# 5V_Regulator.net
KiCad netlist of a schematic drawn in Altium Designer
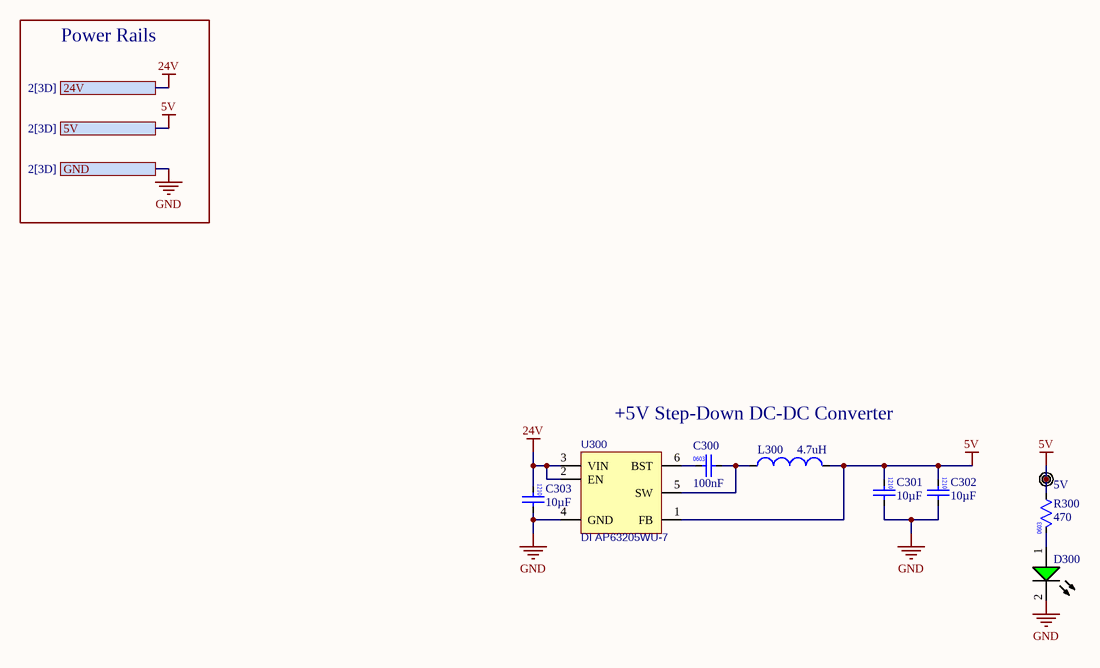
[diagram p0: 5V_Regulator.SchDoc]

(export (version "E")
  (design (tool "Eeschema 10.0.6"))
  (components
    (comp (ref "C300")
      (value "100nF")
      (footprint "0603 Capacitor Footprint")
      (description "CAP CER 0.1UF 50V X7R 0603")
      (fields (field (name "MANUFACTURER PART NUMBER") "CC0603JPX7R9BB104") (field (name "TOLERANCE") "5%"))
      (libsource (lib "UBC Formula Electric") (part "0603 Generic Ceramic Capacitor"))
    )
    (comp (ref "C301")
      (value "10µF")
      (footprint "1210 CAPACTIOR (TDK C-SERIES)")
      (description "Ceramic Capacitor, Multilayer, Ceramic, 50V, 10% Tol, X7R, 15% TC, 10uF, Surface Mount, 1210")
      (fields
        (field (name "TOLERANCE") "10%")
        (field (name "Comment") "1210 10uF 10% 50V")
        (field (name "SOURCE") "UBC Formula Electric.SchLib")
      )
      (libsource (lib "UBC Formula Electric") (part "1210 Generic Ceramic Capacitor"))
    )
    (comp (ref "C302")
      (value "10µF")
      (footprint "1210 CAPACTIOR (TDK C-SERIES)")
      (description "Ceramic Capacitor, Multilayer, Ceramic, 50V, 10% Tol, X7R, 15% TC, 10uF, Surface Mount, 1210")
      (fields
        (field (name "TOLERANCE") "10%")
        (field (name "Comment") "1210 10uF 10% 50V")
        (field (name "SOURCE") "UBC Formula Electric.SchLib")
      )
      (libsource (lib "UBC Formula Electric") (part "1210 Generic Ceramic Capacitor"))
    )
    (comp (ref "C303")
      (value "10µF")
      (footprint "1210 CAPACTIOR (TDK C-SERIES)")
      (description "Ceramic Capacitor, Multilayer, Ceramic, 50V, 10% Tol, X7R, 15% TC, 10uF, Surface Mount, 1210")
      (fields
        (field (name "TOLERANCE") "10%")
        (field (name "Comment") "1210 10uF 10% 50V")
        (field (name "SOURCE") "UBC Formula Electric.SchLib")
      )
      (libsource (lib "UBC Formula Electric") (part "1210 Generic Ceramic Capacitor"))
    )
    (comp (ref "D300")
      (value "Lite-On LTST-C193KGKT-5A")
      (footprint "Lite-On LTST-C193KGKT-5A GREEN (1608)")
      (description "LED GREEN CLEAR CHIP SMD")
      (fields (field (name "SOURCE") "UBC Formula Electric.SchLib"))
      (libsource (lib "UBC Formula Electric") (part "Lite-On LTST-C193KGKT-5A"))
    )
    (comp (ref "L300")
      (value "Bourns SRN6045-4R7Y")
      (footprint "BOURNS SRN6045-4R7Y")
      (description "FIXED IND 4.7UH 3A 37.6 MOHM SMD")
      (fields (field (name "INDUCTANCE") "4.7uH") (field (name "SOURCE") "UBC Formula Electric.SchLib"))
      (libsource (lib "UBC Formula Electric") (part "Symbol"))
    )
    (comp (ref "R300")
      (value "470")
      (footprint "0603 Resistor Footprint")
      (description "Res Thick Film 0603 470 Ohm 5% 0.25W(1/4W) ±200ppm/C Pad SMD Automotive T/R")
      (fields (field (name "TOLERANCE") "5%") (field (name "POWER") "250mW"))
      (libsource (lib "UBC Formula Electric") (part "RES-2"))
    )
    (comp (ref "TP300")
      (value "5V")
      (footprint "TESTPOINT")
      (fields (field (name "SOURCE") "UBC Formula Electric.SchLib"))
      (libsource (lib "UBC Formula Electric") (part "Thru-Hole Test Point"))
    )
    (comp (ref "U300")
      (value "DI AP63205WU-7")
      (footprint "Diodes Incorporated AP63205WU-7")
      (description "IC REG BUCK 5V 2A TSOT26")
      (libsource (lib "UBC Formula Electric") (part "DI AP63205WU-7"))
    )
  )
  (nets
    (net (code "1") (name "5V") (class "Default")
      (node (ref "C301") (pin "2") (pinfunction "2_2") (pintype "passive"))
      (node (ref "C302") (pin "2") (pinfunction "2_2") (pintype "passive"))
      (node (ref "L300") (pin "2") (pinfunction "2_2") (pintype "passive"))
      (node (ref "R300") (pin "1") (pinfunction "1_1") (pintype "passive"))
      (node (ref "TP300") (pin "1") (pinfunction "TP_1") (pintype "passive"))
      (node (ref "U300") (pin "1") (pinfunction "FB_1") (pintype "passive"))
    )
    (net (code "2") (name "24V") (class "Default")
      (node (ref "C303") (pin "2") (pinfunction "2_2") (pintype "passive"))
      (node (ref "U300") (pin "2") (pinfunction "EN_2") (pintype "passive"))
      (node (ref "U300") (pin "3") (pinfunction "VIN_3") (pintype "passive"))
    )
    (net (code "3") (name "GND") (class "Default")
      (node (ref "C301") (pin "1") (pinfunction "1_1") (pintype "passive"))
      (node (ref "C302") (pin "1") (pinfunction "1_1") (pintype "passive"))
      (node (ref "C303") (pin "1") (pinfunction "1_1") (pintype "passive"))
      (node (ref "D300") (pin "2") (pinfunction "K_2") (pintype "passive"))
      (node (ref "U300") (pin "4") (pinfunction "GND_4") (pintype "passive"))
    )
    (net (code "4") (name "Net-(D300-A)") (class "Default")
      (node (ref "D300") (pin "1") (pinfunction "A_1") (pintype "passive"))
      (node (ref "R300") (pin "2") (pinfunction "2_2") (pintype "passive"))
    )
    (net (code "5") (name "Net-(U300-BST)") (class "Default")
      (node (ref "C300") (pin "2") (pinfunction "2_2") (pintype "passive"))
      (node (ref "U300") (pin "6") (pinfunction "BST_6") (pintype "passive"))
    )
    (net (code "6") (name "Net-(U300-SW)") (class "Default")
      (node (ref "C300") (pin "1") (pinfunction "1_1") (pintype "passive"))
      (node (ref "L300") (pin "1") (pinfunction "1_1") (pintype "passive"))
      (node (ref "U300") (pin "5") (pinfunction "SW_5") (pintype "passive"))
    )
  )
)
